# stylophone.net
KiCad netlist of a schematic drawn in EAGLE
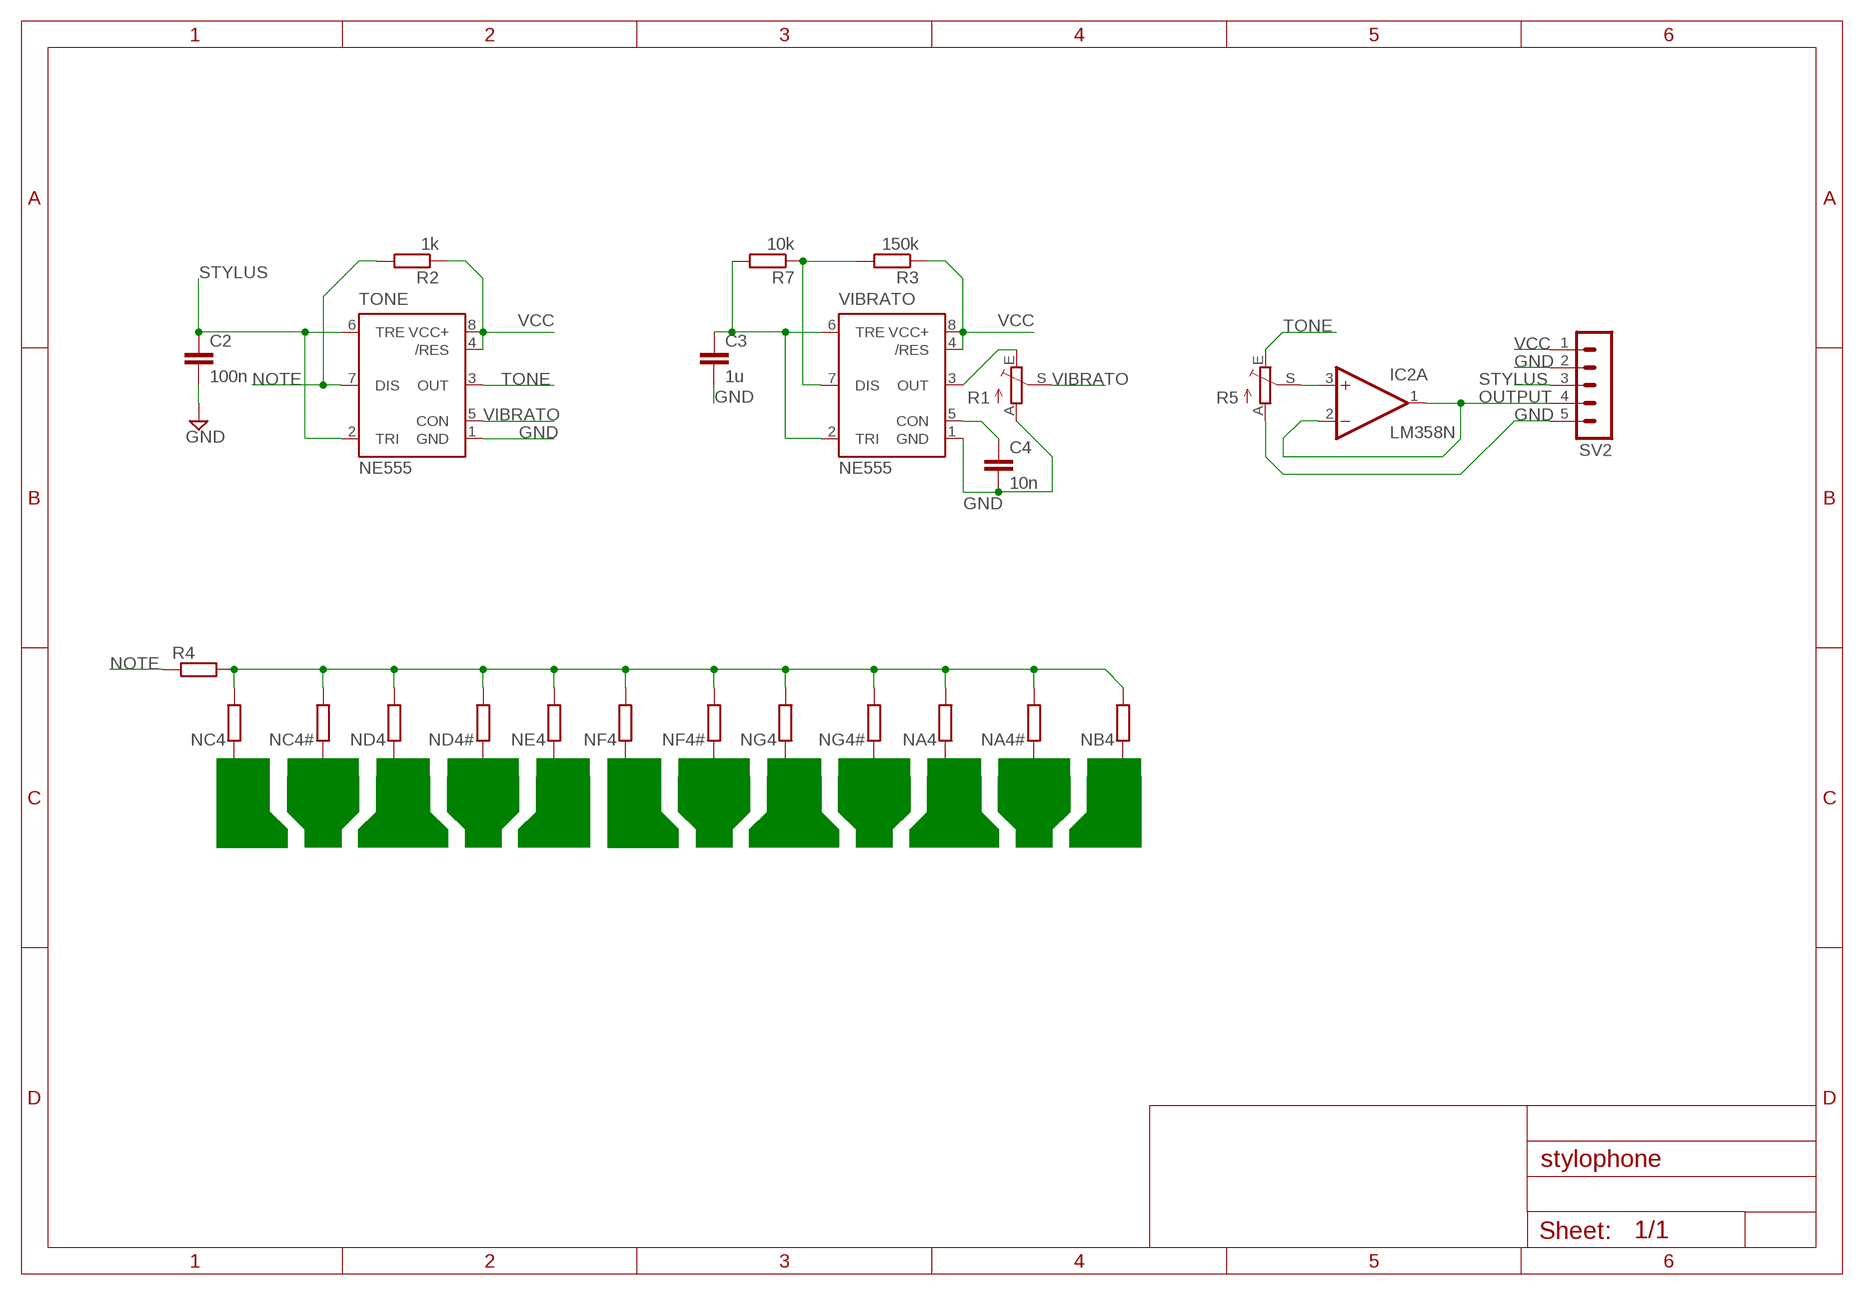
[diagram p0: schematic, sheet 1]

(export (version "E")
  (design (tool "Eeschema 10.0.6"))
  (components
    (comp (ref "C2")
      (value "100n")
      (footprint "eagle-import:C2.5-5")
      (libsource (lib "eagle-import") (part "C2.5/5"))
    )
    (comp (ref "C3")
      (value "1u")
      (footprint "eagle-import:C2.5-5")
      (libsource (lib "eagle-import") (part "C2.5/5"))
    )
    (comp (ref "C4")
      (value "10n")
      (footprint "eagle-import:C2.5-5")
      (libsource (lib "eagle-import") (part "C2.5/5"))
    )
    (comp (ref "IC2")
      (value "LM358N")
      (footprint "eagle-import:DIL08")
      (libsource (lib "eagle-import") (part "LM358N"))
    )
    (comp (ref "NA4")
      (value "R-EU_M1206")
      (footprint "eagle-import:M1206")
      (libsource (lib "eagle-import") (part "resistor_R-EU_M1206"))
    )
    (comp (ref "NA4#")
      (value "R-EU_M1206")
      (footprint "eagle-import:M1206")
      (libsource (lib "eagle-import") (part "resistor_R-EU_M1206"))
    )
    (comp (ref "NB4")
      (value "R-EU_M1206")
      (footprint "eagle-import:M1206")
      (libsource (lib "eagle-import") (part "resistor_R-EU_M1206"))
    )
    (comp (ref "NC4")
      (value "R-EU_M1206")
      (footprint "eagle-import:M1206")
      (libsource (lib "eagle-import") (part "resistor_R-EU_M1206"))
    )
    (comp (ref "NC4#")
      (value "R-EU_M1206")
      (footprint "eagle-import:M1206")
      (libsource (lib "eagle-import") (part "resistor_R-EU_M1206"))
    )
    (comp (ref "ND4")
      (value "R-EU_M1206")
      (footprint "eagle-import:M1206")
      (libsource (lib "eagle-import") (part "resistor_R-EU_M1206"))
    )
    (comp (ref "ND4#")
      (value "R-EU_M1206")
      (footprint "eagle-import:M1206")
      (libsource (lib "eagle-import") (part "resistor_R-EU_M1206"))
    )
    (comp (ref "NE4")
      (value "R-EU_M1206")
      (footprint "eagle-import:M1206")
      (libsource (lib "eagle-import") (part "resistor_R-EU_M1206"))
    )
    (comp (ref "NF4")
      (value "R-EU_M1206")
      (footprint "eagle-import:M1206")
      (libsource (lib "eagle-import") (part "resistor_R-EU_M1206"))
    )
    (comp (ref "NF4#")
      (value "R-EU_M1206")
      (footprint "eagle-import:M1206")
      (libsource (lib "eagle-import") (part "resistor_R-EU_M1206"))
    )
    (comp (ref "NG4")
      (value "R-EU_M1206")
      (footprint "eagle-import:M1206")
      (libsource (lib "eagle-import") (part "resistor_R-EU_M1206"))
    )
    (comp (ref "NG4#")
      (value "R-EU_M1206")
      (footprint "eagle-import:M1206")
      (libsource (lib "eagle-import") (part "resistor_R-EU_M1206"))
    )
    (comp (ref "R1")
      (value "TRIM_EU-CA9V")
      (footprint "eagle-import:CA9V")
      (libsource (lib "eagle-import") (part "TRIM_EU-CA9V"))
    )
    (comp (ref "R2")
      (value "1k")
      (footprint "eagle-import:M1206")
      (libsource (lib "eagle-import") (part "resistor_R-EU_M1206"))
    )
    (comp (ref "R3")
      (value "150k")
      (footprint "eagle-import:M1206")
      (libsource (lib "eagle-import") (part "resistor_R-EU_M1206"))
    )
    (comp (ref "R4")
      (value "R-EU_0204/7")
      (footprint "eagle-import:0204_7")
      (libsource (lib "eagle-import") (part "R-EU_0204/7"))
    )
    (comp (ref "R5")
      (value "TRIM_EU-CA9V")
      (footprint "eagle-import:CA9V")
      (libsource (lib "eagle-import") (part "TRIM_EU-CA9V"))
    )
    (comp (ref "R7")
      (value "10k")
      (footprint "eagle-import:M1206")
      (libsource (lib "eagle-import") (part "resistor_R-EU_M1206"))
    )
    (comp (ref "SV2")
      (value "MA05-1")
      (footprint "eagle-import:MA05-1")
      (libsource (lib "eagle-import") (part "MA05-1"))
    )
    (comp (ref "TONE")
      (value "NE555")
      (footprint "eagle-import:DIL-08")
      (fields (field (name "MF") "Arrow Electronics") (field (name "MPN") "NE555N"))
      (libsource (lib "eagle-import") (part "NE555"))
    )
    (comp (ref "VIBRATO")
      (value "NE555")
      (footprint "eagle-import:DIL-08")
      (fields (field (name "MF") "Arrow Electronics") (field (name "MPN") "NE555N"))
      (libsource (lib "eagle-import") (part "NE555"))
    )
  )
  (nets
    (net (code "1") (name "/NOTE") (class "Default")
      (node (ref "R2") (pin "2") (pinfunction "2_2") (pintype "passive"))
      (node (ref "R4") (pin "1") (pinfunction "1_1") (pintype "passive"))
      (node (ref "TONE") (pin "7") (pinfunction "DIS_7") (pintype "input"))
    )
    (net (code "2") (name "/OUTPUT") (class "Default")
      (node (ref "IC2") (pin "1") (pinfunction "OUT_1") (pintype "output"))
      (node (ref "IC2") (pin "2") (pinfunction "-IN_2") (pintype "input"))
      (node (ref "SV2") (pin "4") (pinfunction "4_4") (pintype "passive"))
    )
    (net (code "3") (name "/STYLUS") (class "Default")
      (node (ref "C2") (pin "1") (pinfunction "1_1") (pintype "passive"))
      (node (ref "SV2") (pin "3") (pinfunction "3_3") (pintype "passive"))
      (node (ref "TONE") (pin "2") (pinfunction "TRI_2") (pintype "input"))
      (node (ref "TONE") (pin "6") (pinfunction "TRE_6") (pintype "input"))
    )
    (net (code "4") (name "/TONE") (class "Default")
      (node (ref "R5") (pin "E") (pinfunction "E_E") (pintype "passive"))
      (node (ref "TONE") (pin "3") (pinfunction "OUT_3") (pintype "output"))
    )
    (net (code "5") (name "/VCC") (class "Default")
      (node (ref "R2") (pin "1") (pinfunction "1_1") (pintype "passive"))
      (node (ref "R3") (pin "1") (pinfunction "1_1") (pintype "passive"))
      (node (ref "SV2") (pin "1") (pinfunction "1_1") (pintype "passive"))
      (node (ref "TONE") (pin "4") (pinfunction "/RES_4") (pintype "input"))
      (node (ref "TONE") (pin "8") (pinfunction "VCC+_8") (pintype "power_in"))
      (node (ref "VIBRATO") (pin "4") (pinfunction "/RES_4") (pintype "input"))
      (node (ref "VIBRATO") (pin "8") (pinfunction "VCC+_8") (pintype "power_in"))
    )
    (net (code "6") (name "/VIBRATO") (class "Default")
      (node (ref "R1") (pin "S") (pinfunction "S_S") (pintype "passive"))
      (node (ref "TONE") (pin "5") (pinfunction "CON_5") (pintype "input"))
    )
    (net (code "7") (name "GND") (class "Default")
      (node (ref "C2") (pin "2") (pinfunction "2_2") (pintype "passive"))
      (node (ref "C3") (pin "2") (pinfunction "2_2") (pintype "passive"))
      (node (ref "C4") (pin "2") (pinfunction "2_2") (pintype "passive"))
      (node (ref "R1") (pin "A") (pinfunction "A_A") (pintype "passive"))
      (node (ref "R5") (pin "A") (pinfunction "A_A") (pintype "passive"))
      (node (ref "SV2") (pin "2") (pinfunction "2_2") (pintype "passive"))
      (node (ref "SV2") (pin "5") (pinfunction "5_5") (pintype "passive"))
      (node (ref "TONE") (pin "1") (pinfunction "GND_1") (pintype "power_in"))
      (node (ref "VIBRATO") (pin "1") (pinfunction "GND_1") (pintype "power_in"))
    )
    (net (code "8") (name "Net-(IC2A-+IN)") (class "Default")
      (node (ref "IC2") (pin "3") (pinfunction "+IN_3") (pintype "input"))
      (node (ref "R5") (pin "S") (pinfunction "S_S") (pintype "passive"))
    )
    (net (code "9") (name "Net-(NA4#-Pad2)") (class "Default")
      (node (ref "NA4") (pin "2") (pinfunction "2_2") (pintype "passive"))
      (node (ref "NA4#") (pin "2") (pinfunction "2_2") (pintype "passive"))
      (node (ref "NB4") (pin "2") (pinfunction "2_2") (pintype "passive"))
      (node (ref "NC4") (pin "2") (pinfunction "2_2") (pintype "passive"))
      (node (ref "NC4#") (pin "2") (pinfunction "2_2") (pintype "passive"))
      (node (ref "ND4") (pin "2") (pinfunction "2_2") (pintype "passive"))
      (node (ref "ND4#") (pin "2") (pinfunction "2_2") (pintype "passive"))
      (node (ref "NE4") (pin "2") (pinfunction "2_2") (pintype "passive"))
      (node (ref "NF4") (pin "2") (pinfunction "2_2") (pintype "passive"))
      (node (ref "NF4#") (pin "2") (pinfunction "2_2") (pintype "passive"))
      (node (ref "NG4") (pin "2") (pinfunction "2_2") (pintype "passive"))
      (node (ref "NG4#") (pin "2") (pinfunction "2_2") (pintype "passive"))
      (node (ref "R4") (pin "2") (pinfunction "2_2") (pintype "passive"))
    )
    (net (code "10") (name "Net-(VIBRATO-CON)") (class "Default")
      (node (ref "C4") (pin "1") (pinfunction "1_1") (pintype "passive"))
      (node (ref "VIBRATO") (pin "5") (pinfunction "CON_5") (pintype "input"))
    )
    (net (code "11") (name "Net-(VIBRATO-DIS)") (class "Default")
      (node (ref "R3") (pin "2") (pinfunction "2_2") (pintype "passive"))
      (node (ref "R7") (pin "1") (pinfunction "1_1") (pintype "passive"))
      (node (ref "VIBRATO") (pin "7") (pinfunction "DIS_7") (pintype "input"))
    )
    (net (code "12") (name "Net-(VIBRATO-OUT)") (class "Default")
      (node (ref "R1") (pin "E") (pinfunction "E_E") (pintype "passive"))
      (node (ref "VIBRATO") (pin "3") (pinfunction "OUT_3") (pintype "output"))
    )
    (net (code "13") (name "Net-(VIBRATO-TRE)") (class "Default")
      (node (ref "C3") (pin "1") (pinfunction "1_1") (pintype "passive"))
      (node (ref "R7") (pin "2") (pinfunction "2_2") (pintype "passive"))
      (node (ref "VIBRATO") (pin "2") (pinfunction "TRI_2") (pintype "input"))
      (node (ref "VIBRATO") (pin "6") (pinfunction "TRE_6") (pintype "input"))
    )
    (net (code "14") (name "unconnected-(NA4#-Pad1)") (class "Default")
      (node (ref "NA4#") (pin "1") (pinfunction "1_1") (pintype "passive"))
    )
    (net (code "15") (name "unconnected-(NA4-Pad1)") (class "Default")
      (node (ref "NA4") (pin "1") (pinfunction "1_1") (pintype "passive"))
    )
    (net (code "16") (name "unconnected-(NB4-Pad1)") (class "Default")
      (node (ref "NB4") (pin "1") (pinfunction "1_1") (pintype "passive"))
    )
    (net (code "17") (name "unconnected-(NC4#-Pad1)") (class "Default")
      (node (ref "NC4#") (pin "1") (pinfunction "1_1") (pintype "passive"))
    )
    (net (code "18") (name "unconnected-(NC4-Pad1)") (class "Default")
      (node (ref "NC4") (pin "1") (pinfunction "1_1") (pintype "passive"))
    )
    (net (code "19") (name "unconnected-(ND4#-Pad1)") (class "Default")
      (node (ref "ND4#") (pin "1") (pinfunction "1_1") (pintype "passive"))
    )
    (net (code "20") (name "unconnected-(ND4-Pad1)") (class "Default")
      (node (ref "ND4") (pin "1") (pinfunction "1_1") (pintype "passive"))
    )
    (net (code "21") (name "unconnected-(NE4-Pad1)") (class "Default")
      (node (ref "NE4") (pin "1") (pinfunction "1_1") (pintype "passive"))
    )
    (net (code "22") (name "unconnected-(NF4#-Pad1)") (class "Default")
      (node (ref "NF4#") (pin "1") (pinfunction "1_1") (pintype "passive"))
    )
    (net (code "23") (name "unconnected-(NF4-Pad1)") (class "Default")
      (node (ref "NF4") (pin "1") (pinfunction "1_1") (pintype "passive"))
    )
    (net (code "24") (name "unconnected-(NG4#-Pad1)") (class "Default")
      (node (ref "NG4#") (pin "1") (pinfunction "1_1") (pintype "passive"))
    )
    (net (code "25") (name "unconnected-(NG4-Pad1)") (class "Default")
      (node (ref "NG4") (pin "1") (pinfunction "1_1") (pintype "passive"))
    )
  )
)
